# CPU.net
KiCad netlist of a schematic drawn in Altium Designer
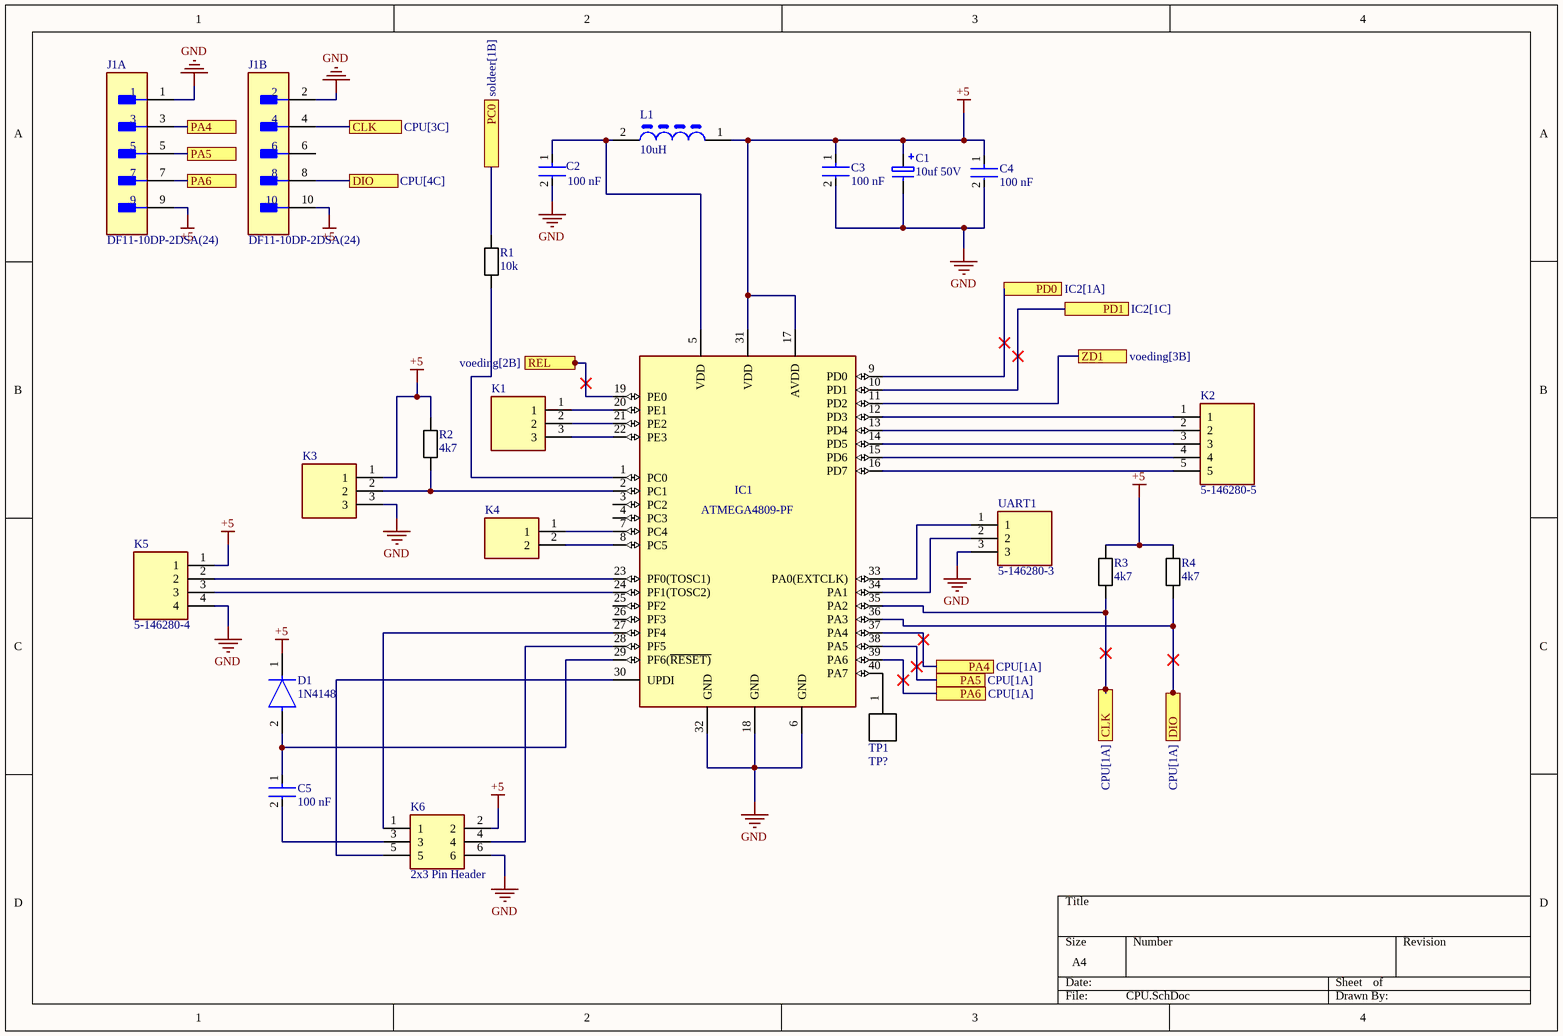
[diagram p0: CPU.SchDoc]

(export (version "E")
  (design (tool "Eeschema 10.0.6"))
  (components
    (comp (ref "C1")
      (value "10uf 50V")
      (footprint "Elco 10uF 50V")
      (fields
        (field (name "PART NUMBER") "02015A270JAT2A")
        (field (name "MANUFACTURER") "AVX Interconnect / Elco")
      )
      (libsource (lib "Schlib1") (part "Condensator 10uf 50V"))
    )
    (comp (ref "C2")
      (value "100 nF")
      (footprint "0805")
      (description "Chip Multilayer Ceramic Capacitors for General Purpose, 0805, 10uF, X5R, 15%, 10%, 25V")
      (fields (field (name "VOLTAGE") "25V") (field (name "TOLERANCE") "10%"))
      (libsource (lib "soldeerstation") (part "Condensator 0805"))
    )
    (comp (ref "C3")
      (value "100 nF")
      (footprint "0805")
      (description "Chip Multilayer Ceramic Capacitors for General Purpose, 0805, 10uF, X5R, 15%, 10%, 25V")
      (fields (field (name "VOLTAGE") "25V") (field (name "TOLERANCE") "10%"))
      (libsource (lib "soldeerstation") (part "Condensator 0805"))
    )
    (comp (ref "C4")
      (value "100 nF")
      (footprint "0805")
      (description "Chip Multilayer Ceramic Capacitors for General Purpose, 0805, 10uF, X5R, 15%, 10%, 25V")
      (fields (field (name "VOLTAGE") "25V") (field (name "TOLERANCE") "10%"))
      (libsource (lib "soldeerstation") (part "Condensator 0805"))
    )
    (comp (ref "C5")
      (value "100 nF")
      (footprint "0805")
      (description "Chip Multilayer Ceramic Capacitors for General Purpose, 0805, 10uF, X5R, 15%, 10%, 25V")
      (fields (field (name "VOLTAGE") "25V") (field (name "TOLERANCE") "10%"))
      (libsource (lib "soldeerstation") (part "Condensator 0805"))
    )
    (comp (ref "D1")
      (value "1N4148")
      (footprint "1N4148")
      (description "DIODE GEN PURP 100V 200MA DO35")
      (fields (field (name "VOLTAGE") "100V"))
      (libsource (lib "soldeerstation") (part "1N4148"))
    )
    (comp (ref "IC1")
      (value "ATMEGA4809-PF")
      (footprint "FP-C04-016-MFG")
      (description "IC MCU 8BIT 48KB FLASH 40DIP")
      (libsource (lib "soldeerstation") (part "CMP-06276-000616-1"))
    )
    (comp (ref "J1")
      (value "DF11-10DP-2DSA(24)")
      (footprint "FP-DF11-10DP-2DSA_24-MFG - duplicate")
      (description "CONN HEADER VERT 10POS 2MM")
      (fields
        (field (name "OCTOPART") "https://octopart.com/df11-10dp-2dsa%2824%29-hirose-39521433")
        (field (name "MANUFACTURER") "Hirose")
      )
      (libsource (lib "Schlib1") (part "CMP-11610-000008-1"))
    )
    (comp (ref "K1")
      (value "5-146280-3")
      (footprint "3 Pin Header")
      (description "Connector 5-146280-3")
      (fields (field (name "MOUSER2 PART NUMBER") "571-5-146280-3"))
      (libsource (lib "") (part "3 Pin Header L_1"))
    )
    (comp (ref "K2")
      (value "5-146280-5")
      (footprint "5 Pin Header")
      (description "Connector 5-146280-5")
      (fields (field (name "MOUSER2 PART NUMBER") "571-5-146280-5"))
      (libsource (lib "soldeerstation") (part "5 Pin Header"))
    )
    (comp (ref "K3")
      (value "5-146280-3")
      (footprint "3 Pin Header")
      (description "Connector 5-146280-3")
      (fields (field (name "MOUSER2 PART NUMBER") "571-5-146280-3"))
      (libsource (lib "") (part "3 Pin Header L_1"))
    )
    (comp (ref "K4")
      (value "5-146280-2")
      (footprint "2 Pin Header")
      (description "Connector")
      (libsource (lib "soldeerstation") (part "2 Pin Header L"))
    )
    (comp (ref "K5")
      (value "5-146280-4")
      (footprint "4 Pin Header")
      (description "Connector 5-146280-4")
      (libsource (lib "soldeerstation") (part "4 Pin Header L"))
    )
    (comp (ref "K6")
      (value "2x3 Pin Header")
      (footprint "2x3 Pin Header")
      (description "Connector")
      (fields (field (name "MANUFACTURER_PART_NUMBER") "5-146256-3"))
      (libsource (lib "soldeerstation") (part "2x3 Pin Header"))
    )
    (comp (ref "L1")
      (value "10uH")
      (footprint "Smoorspoel")
      (description "Inductor VLS6045EX-100M-H")
      (fields
        (field (name "MOUSER2 PART NUMBER") "810-VLS6045EX-100M-H")
        (field (name "MANUFACTURER_PART_NUMBER") "VLS6045EX-100M-H")
      )
      (libsource (lib "soldeerstation") (part "Smoorspoel"))
    )
    (comp (ref "R1")
      (value "10k")
      (footprint "registor")
      (fields (field (name "MANUFACTURER") "Vishay Dale") (field (name "PART NUMBER") "CRCW08050000Z0EA"))
      (libsource (lib "Schlib1") (part "resistor"))
    )
    (comp (ref "R2")
      (value "4k7")
      (footprint "registor")
      (fields (field (name "MANUFACTURER") "Vishay Dale") (field (name "PART NUMBER") "CRCW08050000Z0EA"))
      (libsource (lib "Schlib1") (part "resistor"))
    )
    (comp (ref "R3")
      (value "4k7")
      (footprint "registor")
      (fields (field (name "MANUFACTURER") "Vishay Dale") (field (name "PART NUMBER") "CRCW08050000Z0EA"))
      (libsource (lib "Schlib1") (part "resistor"))
    )
    (comp (ref "R4")
      (value "4k7")
      (footprint "registor")
      (fields (field (name "MANUFACTURER") "Vishay Dale") (field (name "PART NUMBER") "CRCW08050000Z0EA"))
      (libsource (lib "Schlib1") (part "resistor"))
    )
    (comp (ref "TP1") (value "TP?") (footprint "testpunt") (libsource (lib "Schlib1") (part "testpunt")))
    (comp (ref "UART1")
      (value "5-146280-3")
      (footprint "3 Pin Header")
      (description "Connector 5-146280-3")
      (fields (field (name "MOUSER2 PART NUMBER") "571-5-146280-3"))
      (libsource (lib "soldeerstation") (part "3 Pin Header L"))
    )
  )
  (nets
    (net (code "1") (name "+5") (class "Default")
      (node (ref "C1") (pin "1") (pinfunction "1_1") (pintype "passive"))
      (node (ref "C3") (pin "1") (pinfunction "1_1") (pintype "passive"))
      (node (ref "C4") (pin "1") (pinfunction "1_1") (pintype "passive"))
      (node (ref "D1") (pin "1") (pinfunction "C_1") (pintype "passive"))
      (node (ref "IC1") (pin "17") (pinfunction "AVDD_17") (pintype "power_in"))
      (node (ref "IC1") (pin "31") (pinfunction "VDD_31") (pintype "power_in"))
      (node (ref "J1") (pin "10") (pinfunction "10_10") (pintype "passive"))
      (node (ref "J1") (pin "9") (pinfunction "9_9") (pintype "passive"))
      (node (ref "K3") (pin "1") (pinfunction "1_1") (pintype "passive"))
      (node (ref "K5") (pin "1") (pinfunction "1_1") (pintype "passive"))
      (node (ref "K6") (pin "2") (pinfunction "2_2") (pintype "passive"))
      (node (ref "L1") (pin "1") (pinfunction "1_1") (pintype "passive"))
      (node (ref "R2") (pin "2") (pinfunction "2_2") (pintype "passive"))
      (node (ref "R3") (pin "2") (pinfunction "2_2") (pintype "passive"))
      (node (ref "R4") (pin "2") (pinfunction "2_2") (pintype "passive"))
    )
    (net (code "2") (name "/CLK") (class "Default")
      (node (ref "IC1") (pin "35") (pinfunction "PA2_35") (pintype "bidirectional"))
      (node (ref "J1") (pin "4") (pinfunction "4_4") (pintype "passive"))
      (node (ref "R3") (pin "1") (pinfunction "1_1") (pintype "passive"))
    )
    (net (code "3") (name "/DIO") (class "Default")
      (node (ref "IC1") (pin "36") (pinfunction "PA3_36") (pintype "bidirectional"))
      (node (ref "J1") (pin "8") (pinfunction "8_8") (pintype "passive"))
      (node (ref "R4") (pin "1") (pinfunction "1_1") (pintype "passive"))
    )
    (net (code "4") (name "/PA4") (class "Default")
      (node (ref "IC1") (pin "37") (pinfunction "PA4_37") (pintype "bidirectional"))
      (node (ref "J1") (pin "3") (pinfunction "3_3") (pintype "passive"))
    )
    (net (code "5") (name "/PA5") (class "Default")
      (node (ref "IC1") (pin "38") (pinfunction "PA5_38") (pintype "bidirectional"))
      (node (ref "J1") (pin "5") (pinfunction "5_5") (pintype "passive"))
    )
    (net (code "6") (name "/PA6") (class "Default")
      (node (ref "IC1") (pin "39") (pinfunction "PA6_39") (pintype "bidirectional"))
      (node (ref "J1") (pin "7") (pinfunction "7_7") (pintype "passive"))
    )
    (net (code "7") (name "/PC0") (class "Default")
      (node (ref "R1") (pin "2") (pinfunction "2_2") (pintype "passive"))
    )
    (net (code "8") (name "/PD0") (class "Default")
      (node (ref "IC1") (pin "9") (pinfunction "PD0_9") (pintype "bidirectional"))
    )
    (net (code "9") (name "/PD1") (class "Default")
      (node (ref "IC1") (pin "10") (pinfunction "PD1_10") (pintype "bidirectional"))
    )
    (net (code "10") (name "/REL") (class "Default")
      (node (ref "IC1") (pin "19") (pinfunction "PE0_19") (pintype "bidirectional"))
    )
    (net (code "11") (name "/ZD1") (class "Default")
      (node (ref "IC1") (pin "11") (pinfunction "PD2_11") (pintype "bidirectional"))
    )
    (net (code "12") (name "GND") (class "Default")
      (node (ref "C1") (pin "2") (pinfunction "2_2") (pintype "passive"))
      (node (ref "C2") (pin "2") (pinfunction "2_2") (pintype "passive"))
      (node (ref "C3") (pin "2") (pinfunction "2_2") (pintype "passive"))
      (node (ref "C4") (pin "2") (pinfunction "2_2") (pintype "passive"))
      (node (ref "IC1") (pin "18") (pinfunction "GND_18") (pintype "power_in"))
      (node (ref "IC1") (pin "32") (pinfunction "GND_32") (pintype "power_in"))
      (node (ref "IC1") (pin "6") (pinfunction "GND_6") (pintype "power_in"))
      (node (ref "J1") (pin "1") (pinfunction "1_1") (pintype "passive"))
      (node (ref "J1") (pin "2") (pinfunction "2_2") (pintype "passive"))
      (node (ref "K3") (pin "3") (pinfunction "3_3") (pintype "passive"))
      (node (ref "K5") (pin "4") (pinfunction "4_4") (pintype "passive"))
      (node (ref "K6") (pin "6") (pinfunction "6_6") (pintype "passive"))
      (node (ref "UART1") (pin "3") (pinfunction "3_3") (pintype "passive"))
    )
    (net (code "13") (name "Net-(C2-Pad1)") (class "Default")
      (node (ref "C2") (pin "1") (pinfunction "1_1") (pintype "passive"))
      (node (ref "IC1") (pin "5") (pinfunction "VDD_5") (pintype "power_in"))
      (node (ref "L1") (pin "2") (pinfunction "2_2") (pintype "passive"))
    )
    (net (code "14") (name "Net-(C5-Pad2)") (class "Default")
      (node (ref "C5") (pin "2") (pinfunction "2_2") (pintype "passive"))
      (node (ref "K6") (pin "3") (pinfunction "3_3") (pintype "passive"))
    )
    (net (code "15") (name "Net-(D1-A)") (class "Default")
      (node (ref "C5") (pin "1") (pinfunction "1_1") (pintype "passive"))
      (node (ref "D1") (pin "2") (pinfunction "A_2") (pintype "passive"))
      (node (ref "IC1") (pin "29") (pinfunction "PF6(~{RESET)}_29") (pintype "bidirectional"))
    )
    (net (code "16") (name "Net-(IC1-PA0(EXTCLK))") (class "Default")
      (node (ref "IC1") (pin "33") (pinfunction "PA0(EXTCLK)_33") (pintype "bidirectional"))
      (node (ref "UART1") (pin "1") (pinfunction "1_1") (pintype "passive"))
    )
    (net (code "17") (name "Net-(IC1-PA1)") (class "Default")
      (node (ref "IC1") (pin "34") (pinfunction "PA1_34") (pintype "bidirectional"))
      (node (ref "UART1") (pin "2") (pinfunction "2_2") (pintype "passive"))
    )
    (net (code "18") (name "Net-(IC1-PA7)") (class "Default")
      (node (ref "IC1") (pin "40") (pinfunction "PA7_40") (pintype "bidirectional"))
      (node (ref "TP1") (pin "1") (pintype "passive"))
    )
    (net (code "19") (name "Net-(IC1-PC0)") (class "Default")
      (node (ref "IC1") (pin "1") (pinfunction "PC0_1") (pintype "bidirectional"))
      (node (ref "R1") (pin "1") (pinfunction "1_1") (pintype "passive"))
    )
    (net (code "20") (name "Net-(IC1-PC1)") (class "Default")
      (node (ref "IC1") (pin "2") (pinfunction "PC1_2") (pintype "bidirectional"))
      (node (ref "K3") (pin "2") (pinfunction "2_2") (pintype "passive"))
      (node (ref "R2") (pin "1") (pinfunction "1_1") (pintype "passive"))
    )
    (net (code "21") (name "Net-(IC1-PC4)") (class "Default")
      (node (ref "IC1") (pin "7") (pinfunction "PC4_7") (pintype "bidirectional"))
      (node (ref "K4") (pin "1") (pinfunction "1_1") (pintype "passive"))
    )
    (net (code "22") (name "Net-(IC1-PC5)") (class "Default")
      (node (ref "IC1") (pin "8") (pinfunction "PC5_8") (pintype "bidirectional"))
      (node (ref "K4") (pin "2") (pinfunction "2_2") (pintype "passive"))
    )
    (net (code "23") (name "Net-(IC1-PD3)") (class "Default")
      (node (ref "IC1") (pin "12") (pinfunction "PD3_12") (pintype "bidirectional"))
      (node (ref "K2") (pin "1") (pinfunction "1_1") (pintype "passive"))
    )
    (net (code "24") (name "Net-(IC1-PD4)") (class "Default")
      (node (ref "IC1") (pin "13") (pinfunction "PD4_13") (pintype "bidirectional"))
      (node (ref "K2") (pin "2") (pinfunction "2_2") (pintype "passive"))
    )
    (net (code "25") (name "Net-(IC1-PD5)") (class "Default")
      (node (ref "IC1") (pin "14") (pinfunction "PD5_14") (pintype "bidirectional"))
      (node (ref "K2") (pin "3") (pinfunction "3_3") (pintype "passive"))
    )
    (net (code "26") (name "Net-(IC1-PD6)") (class "Default")
      (node (ref "IC1") (pin "15") (pinfunction "PD6_15") (pintype "bidirectional"))
      (node (ref "K2") (pin "4") (pinfunction "4_4") (pintype "passive"))
    )
    (net (code "27") (name "Net-(IC1-PD7)") (class "Default")
      (node (ref "IC1") (pin "16") (pinfunction "PD7_16") (pintype "bidirectional"))
      (node (ref "K2") (pin "5") (pinfunction "5_5") (pintype "passive"))
    )
    (net (code "28") (name "Net-(IC1-PE1)") (class "Default")
      (node (ref "IC1") (pin "20") (pinfunction "PE1_20") (pintype "bidirectional"))
      (node (ref "K1") (pin "1") (pinfunction "1_1") (pintype "passive"))
    )
    (net (code "29") (name "Net-(IC1-PE2)") (class "Default")
      (node (ref "IC1") (pin "21") (pinfunction "PE2_21") (pintype "bidirectional"))
      (node (ref "K1") (pin "2") (pinfunction "2_2") (pintype "passive"))
    )
    (net (code "30") (name "Net-(IC1-PE3)") (class "Default")
      (node (ref "IC1") (pin "22") (pinfunction "PE3_22") (pintype "bidirectional"))
      (node (ref "K1") (pin "3") (pinfunction "3_3") (pintype "passive"))
    )
    (net (code "31") (name "Net-(IC1-PF0(TOSC1))") (class "Default")
      (node (ref "IC1") (pin "23") (pinfunction "PF0(TOSC1)_23") (pintype "bidirectional"))
      (node (ref "K5") (pin "2") (pinfunction "2_2") (pintype "passive"))
    )
    (net (code "32") (name "Net-(IC1-PF1(TOSC2))") (class "Default")
      (node (ref "IC1") (pin "24") (pinfunction "PF1(TOSC2)_24") (pintype "bidirectional"))
      (node (ref "K5") (pin "3") (pinfunction "3_3") (pintype "passive"))
    )
    (net (code "33") (name "Net-(IC1-PF4)") (class "Default")
      (node (ref "IC1") (pin "27") (pinfunction "PF4_27") (pintype "bidirectional"))
      (node (ref "K6") (pin "1") (pinfunction "1_1") (pintype "passive"))
    )
    (net (code "34") (name "Net-(IC1-PF5)") (class "Default")
      (node (ref "IC1") (pin "28") (pinfunction "PF5_28") (pintype "bidirectional"))
      (node (ref "K6") (pin "4") (pinfunction "4_4") (pintype "passive"))
    )
    (net (code "35") (name "Net-(IC1-UPDI)") (class "Default")
      (node (ref "IC1") (pin "30") (pinfunction "UPDI_30") (pintype "passive"))
      (node (ref "K6") (pin "5") (pinfunction "5_5") (pintype "passive"))
    )
    (net (code "36") (name "unconnected-(IC1-PC2-Pad3)") (class "Default")
      (node (ref "IC1") (pin "3") (pinfunction "PC2_3") (pintype "bidirectional"))
    )
    (net (code "37") (name "unconnected-(IC1-PC3-Pad4)") (class "Default")
      (node (ref "IC1") (pin "4") (pinfunction "PC3_4") (pintype "bidirectional"))
    )
    (net (code "38") (name "unconnected-(IC1-PF2-Pad25)") (class "Default")
      (node (ref "IC1") (pin "25") (pinfunction "PF2_25") (pintype "bidirectional"))
    )
    (net (code "39") (name "unconnected-(IC1-PF3-Pad26)") (class "Default")
      (node (ref "IC1") (pin "26") (pinfunction "PF3_26") (pintype "bidirectional"))
    )
    (net (code "40") (name "unconnected-(J1-Pad6)") (class "Default")
      (node (ref "J1") (pin "6") (pinfunction "6_6") (pintype "passive"))
    )
  )
)
